# perspection-rf-v1.net
KiCad netlist of a schematic drawn in EAGLE
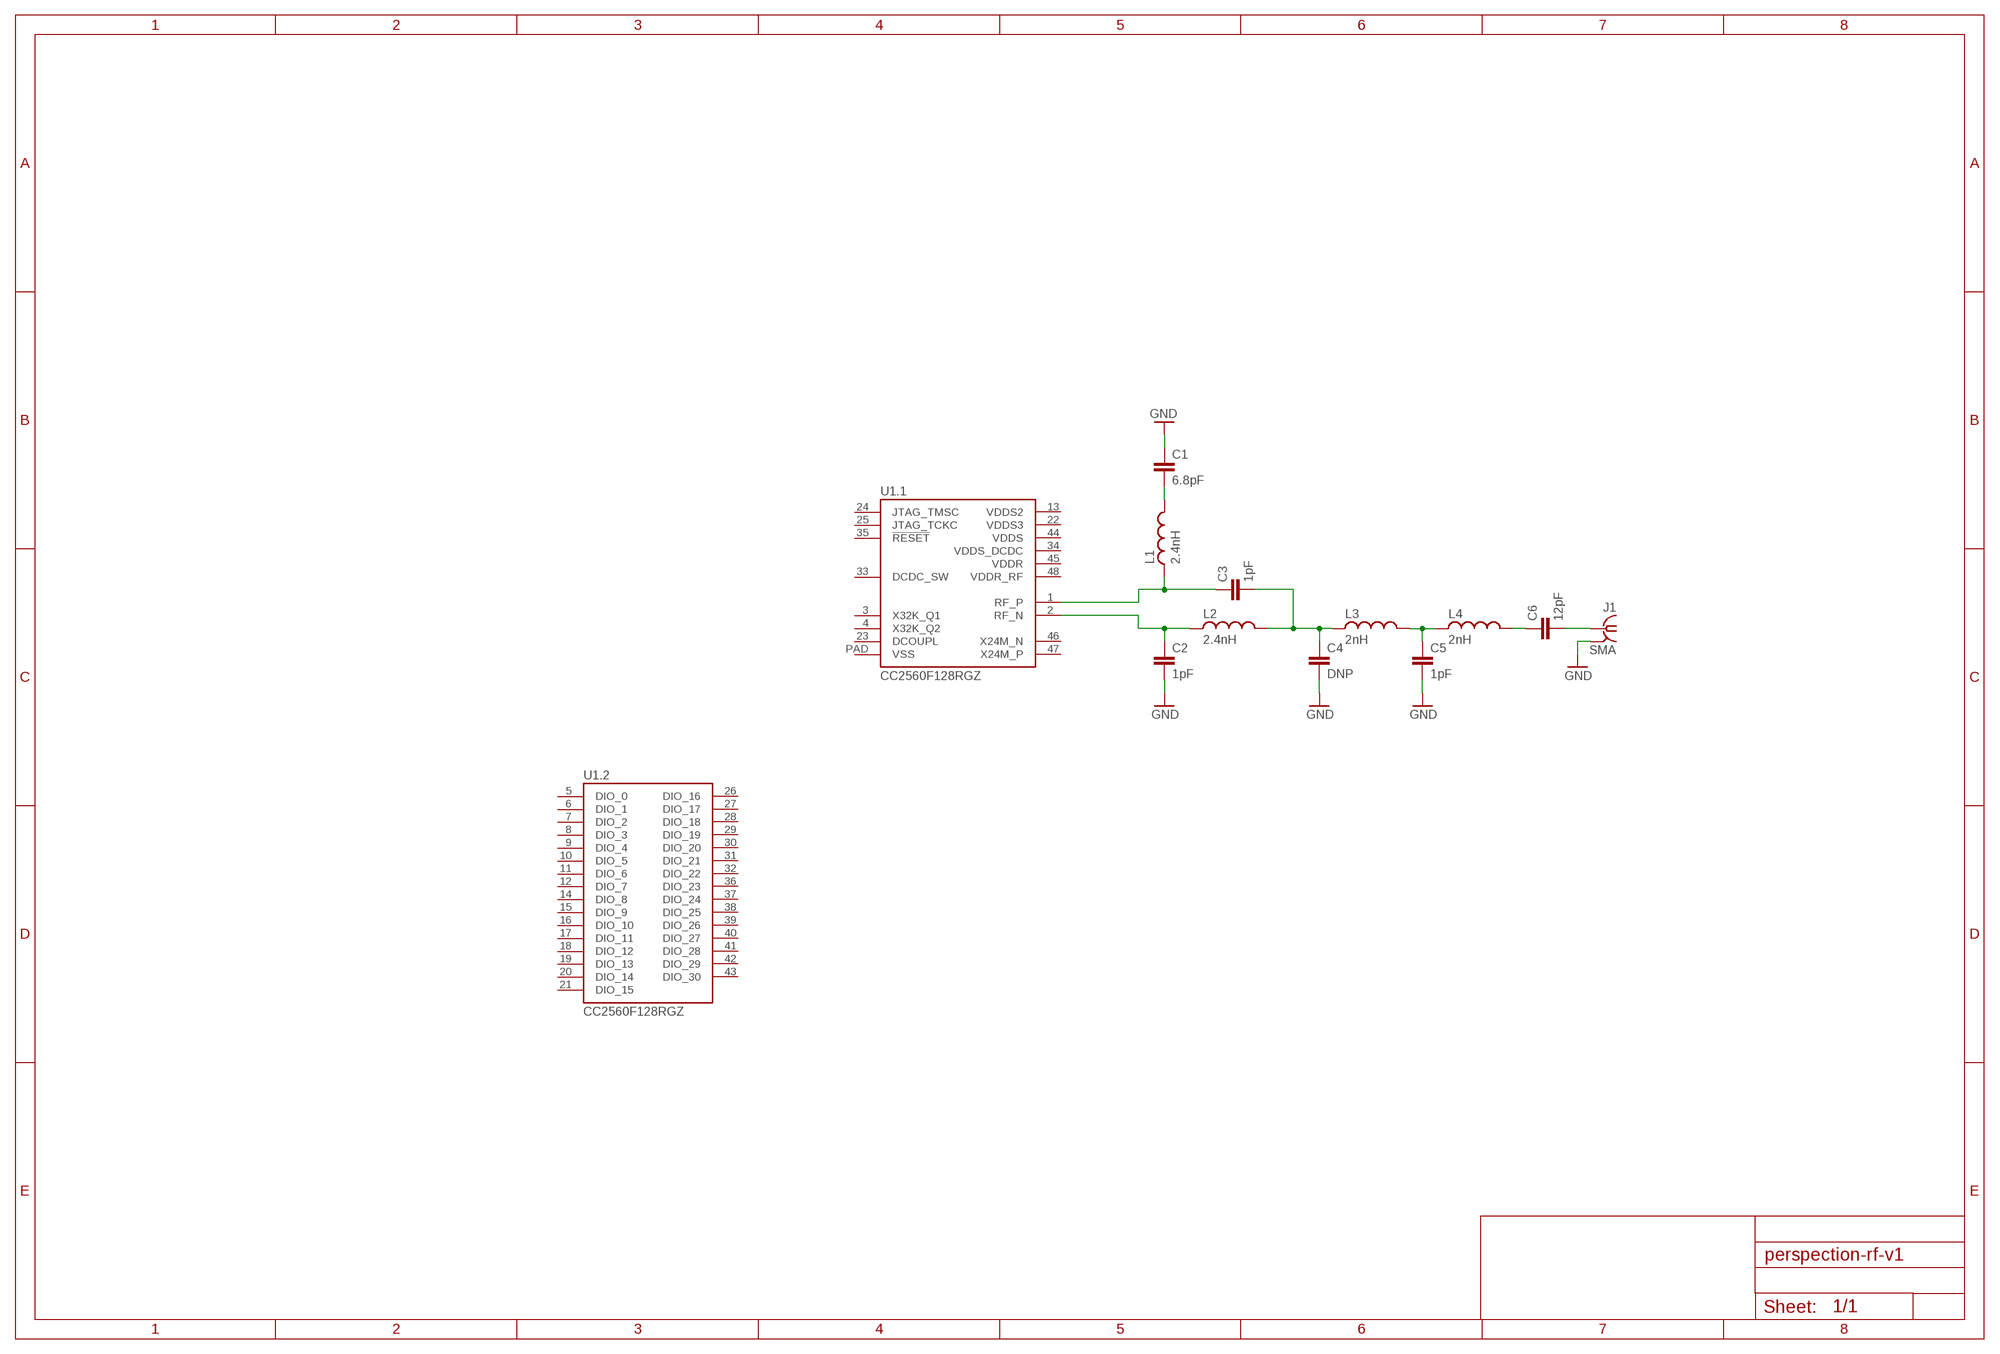
[diagram p0: schematic, sheet 1]

(export (version "E")
  (design (tool "Eeschema 10.0.6"))
  (components
    (comp (ref "C1")
      (value "6.8pF")
      (footprint "eagle-import:C0402")
      (libsource (lib "eagle-import") (part "C0402"))
    )
    (comp (ref "C2")
      (value "1pF")
      (footprint "eagle-import:C0402")
      (libsource (lib "eagle-import") (part "C0402"))
    )
    (comp (ref "C3")
      (value "1pF")
      (footprint "eagle-import:C0402")
      (libsource (lib "eagle-import") (part "C0402"))
    )
    (comp (ref "C4")
      (value "DNP")
      (footprint "eagle-import:C0402")
      (libsource (lib "eagle-import") (part "C0402"))
    )
    (comp (ref "C5")
      (value "1pF")
      (footprint "eagle-import:C0402")
      (libsource (lib "eagle-import") (part "C0402"))
    )
    (comp (ref "C6")
      (value "12pF")
      (footprint "eagle-import:C0402")
      (libsource (lib "eagle-import") (part "C0402"))
    )
    (comp (ref "J1")
      (value "SMA")
      (footprint "eagle-import:SMA-VERT")
      (libsource (lib "eagle-import") (part "SMA"))
    )
    (comp (ref "L1")
      (value "2.4nH")
      (footprint "eagle-import:L0402")
      (libsource (lib "eagle-import") (part "L0402"))
    )
    (comp (ref "L2")
      (value "2.4nH")
      (footprint "eagle-import:L0402")
      (libsource (lib "eagle-import") (part "L0402"))
    )
    (comp (ref "L3")
      (value "2nH")
      (footprint "eagle-import:L0402")
      (libsource (lib "eagle-import") (part "L0402"))
    )
    (comp (ref "L4")
      (value "2nH")
      (footprint "eagle-import:L0402")
      (libsource (lib "eagle-import") (part "L0402"))
    )
    (comp (ref "U1")
      (value "CC2560F128RGZ")
      (footprint "eagle-import:TI-VQFN-48")
      (libsource (lib "eagle-import") (part "CC2560F128RGZ"))
    )
  )
  (nets
    (net (code "1") (name "GND") (class "Default")
      (node (ref "C1") (pin "1") (pinfunction "1_1") (pintype "passive"))
      (node (ref "C2") (pin "2") (pinfunction "2_2") (pintype "passive"))
      (node (ref "C4") (pin "2") (pinfunction "2_2") (pintype "passive"))
      (node (ref "C5") (pin "2") (pinfunction "2_2") (pintype "passive"))
      (node (ref "J1") (pin "NEG1") (pinfunction "NEG_NEG1") (pintype "passive"))
      (node (ref "J1") (pin "NEG2") (pinfunction "NEG_NEG2") (pintype "passive"))
      (node (ref "J1") (pin "NEG3") (pinfunction "NEG_NEG3") (pintype "passive"))
      (node (ref "J1") (pin "NEG4") (pinfunction "NEG_NEG4") (pintype "passive"))
    )
    (net (code "2") (name "Net-(C1-Pad2)") (class "Default")
      (node (ref "C1") (pin "2") (pinfunction "2_2") (pintype "passive"))
      (node (ref "L1") (pin "2") (pinfunction "2_2") (pintype "passive"))
    )
    (net (code "3") (name "Net-(C3-Pad2)") (class "Default")
      (node (ref "C3") (pin "2") (pinfunction "2_2") (pintype "passive"))
      (node (ref "C4") (pin "1") (pinfunction "1_1") (pintype "passive"))
      (node (ref "L2") (pin "2") (pinfunction "2_2") (pintype "passive"))
      (node (ref "L3") (pin "1") (pinfunction "1_1") (pintype "passive"))
    )
    (net (code "4") (name "Net-(C5-Pad1)") (class "Default")
      (node (ref "C5") (pin "1") (pinfunction "1_1") (pintype "passive"))
      (node (ref "L3") (pin "2") (pinfunction "2_2") (pintype "passive"))
      (node (ref "L4") (pin "1") (pinfunction "1_1") (pintype "passive"))
    )
    (net (code "5") (name "Net-(C6-Pad1)") (class "Default")
      (node (ref "C6") (pin "1") (pinfunction "1_1") (pintype "passive"))
      (node (ref "L4") (pin "2") (pinfunction "2_2") (pintype "passive"))
    )
    (net (code "6") (name "Net-(C6-Pad2)") (class "Default")
      (node (ref "C6") (pin "2") (pinfunction "2_2") (pintype "passive"))
      (node (ref "J1") (pin "POS") (pinfunction "POS_POS") (pintype "passive"))
    )
    (net (code "7") (name "Net-(U1A-RF_N)") (class "Default")
      (node (ref "C2") (pin "1") (pinfunction "1_1") (pintype "passive"))
      (node (ref "L2") (pin "1") (pinfunction "1_1") (pintype "passive"))
      (node (ref "U1") (pin "2") (pinfunction "RF_N_2") (pintype "bidirectional"))
    )
    (net (code "8") (name "Net-(U1A-RF_P)") (class "Default")
      (node (ref "C3") (pin "1") (pinfunction "1_1") (pintype "passive"))
      (node (ref "L1") (pin "1") (pinfunction "1_1") (pintype "passive"))
      (node (ref "U1") (pin "1") (pinfunction "RF_P_1") (pintype "bidirectional"))
    )
    (net (code "9") (name "unconnected-(U1A-DCDC_SW-Pad33)") (class "Default")
      (node (ref "U1") (pin "33") (pinfunction "DCDC_SW_33") (pintype "bidirectional"))
    )
    (net (code "10") (name "unconnected-(U1A-DCOUPL-Pad23)") (class "Default")
      (node (ref "U1") (pin "23") (pinfunction "DCOUPL_23") (pintype "bidirectional"))
    )
    (net (code "11") (name "unconnected-(U1A-JTAG_TCKC-Pad25)") (class "Default")
      (node (ref "U1") (pin "25") (pinfunction "JTAG_TCKC_25") (pintype "bidirectional"))
    )
    (net (code "12") (name "unconnected-(U1A-JTAG_TMSC-Pad24)") (class "Default")
      (node (ref "U1") (pin "24") (pinfunction "JTAG_TMSC_24") (pintype "bidirectional"))
    )
    (net (code "13") (name "unconnected-(U1A-VDDR-Pad45)") (class "Default")
      (node (ref "U1") (pin "45") (pinfunction "VDDR_45") (pintype "bidirectional"))
    )
    (net (code "14") (name "unconnected-(U1A-VDDR_RF-Pad48)") (class "Default")
      (node (ref "U1") (pin "48") (pinfunction "VDDR_RF_48") (pintype "bidirectional"))
    )
    (net (code "15") (name "unconnected-(U1A-VDDS-Pad44)") (class "Default")
      (node (ref "U1") (pin "44") (pinfunction "VDDS_44") (pintype "bidirectional"))
    )
    (net (code "16") (name "unconnected-(U1A-VDDS2-Pad13)") (class "Default")
      (node (ref "U1") (pin "13") (pinfunction "VDDS2_13") (pintype "bidirectional"))
    )
    (net (code "17") (name "unconnected-(U1A-VDDS3-Pad22)") (class "Default")
      (node (ref "U1") (pin "22") (pinfunction "VDDS3_22") (pintype "bidirectional"))
    )
    (net (code "18") (name "unconnected-(U1A-VDDS_DCDC-Pad34)") (class "Default")
      (node (ref "U1") (pin "34") (pinfunction "VDDS_DCDC_34") (pintype "bidirectional"))
    )
    (net (code "19") (name "unconnected-(U1A-VSS-PadPAD)") (class "Default")
      (node (ref "U1") (pin "PAD") (pinfunction "VSS_PAD") (pintype "bidirectional"))
    )
    (net (code "20") (name "unconnected-(U1A-X24M_N-Pad46)") (class "Default")
      (node (ref "U1") (pin "46") (pinfunction "X24M_N_46") (pintype "bidirectional"))
    )
    (net (code "21") (name "unconnected-(U1A-X24M_P-Pad47)") (class "Default")
      (node (ref "U1") (pin "47") (pinfunction "X24M_P_47") (pintype "bidirectional"))
    )
    (net (code "22") (name "unconnected-(U1A-X32K_Q1-Pad3)") (class "Default")
      (node (ref "U1") (pin "3") (pinfunction "X32K_Q1_3") (pintype "bidirectional"))
    )
    (net (code "23") (name "unconnected-(U1A-X32K_Q2-Pad4)") (class "Default")
      (node (ref "U1") (pin "4") (pinfunction "X32K_Q2_4") (pintype "bidirectional"))
    )
    (net (code "24") (name "unconnected-(U1A-~{RESET}-Pad35)") (class "Default")
      (node (ref "U1") (pin "35") (pinfunction "~{RESET}_35") (pintype "bidirectional"))
    )
    (net (code "25") (name "unconnected-(U1B-DIO_0-Pad5)") (class "Default")
      (node (ref "U1") (pin "5") (pinfunction "DIO_0_5") (pintype "bidirectional"))
    )
    (net (code "26") (name "unconnected-(U1B-DIO_1-Pad6)") (class "Default")
      (node (ref "U1") (pin "6") (pinfunction "DIO_1_6") (pintype "bidirectional"))
    )
    (net (code "27") (name "unconnected-(U1B-DIO_2-Pad7)") (class "Default")
      (node (ref "U1") (pin "7") (pinfunction "DIO_2_7") (pintype "bidirectional"))
    )
    (net (code "28") (name "unconnected-(U1B-DIO_3-Pad8)") (class "Default")
      (node (ref "U1") (pin "8") (pinfunction "DIO_3_8") (pintype "bidirectional"))
    )
    (net (code "29") (name "unconnected-(U1B-DIO_4-Pad9)") (class "Default")
      (node (ref "U1") (pin "9") (pinfunction "DIO_4_9") (pintype "bidirectional"))
    )
    (net (code "30") (name "unconnected-(U1B-DIO_5-Pad10)") (class "Default")
      (node (ref "U1") (pin "10") (pinfunction "DIO_5_10") (pintype "bidirectional"))
    )
    (net (code "31") (name "unconnected-(U1B-DIO_6-Pad11)") (class "Default")
      (node (ref "U1") (pin "11") (pinfunction "DIO_6_11") (pintype "bidirectional"))
    )
    (net (code "32") (name "unconnected-(U1B-DIO_7-Pad12)") (class "Default")
      (node (ref "U1") (pin "12") (pinfunction "DIO_7_12") (pintype "bidirectional"))
    )
    (net (code "33") (name "unconnected-(U1B-DIO_8-Pad14)") (class "Default")
      (node (ref "U1") (pin "14") (pinfunction "DIO_8_14") (pintype "bidirectional"))
    )
    (net (code "34") (name "unconnected-(U1B-DIO_9-Pad15)") (class "Default")
      (node (ref "U1") (pin "15") (pinfunction "DIO_9_15") (pintype "bidirectional"))
    )
    (net (code "35") (name "unconnected-(U1B-DIO_10-Pad16)") (class "Default")
      (node (ref "U1") (pin "16") (pinfunction "DIO_10_16") (pintype "bidirectional"))
    )
    (net (code "36") (name "unconnected-(U1B-DIO_11-Pad17)") (class "Default")
      (node (ref "U1") (pin "17") (pinfunction "DIO_11_17") (pintype "bidirectional"))
    )
    (net (code "37") (name "unconnected-(U1B-DIO_12-Pad18)") (class "Default")
      (node (ref "U1") (pin "18") (pinfunction "DIO_12_18") (pintype "bidirectional"))
    )
    (net (code "38") (name "unconnected-(U1B-DIO_13-Pad19)") (class "Default")
      (node (ref "U1") (pin "19") (pinfunction "DIO_13_19") (pintype "bidirectional"))
    )
    (net (code "39") (name "unconnected-(U1B-DIO_14-Pad20)") (class "Default")
      (node (ref "U1") (pin "20") (pinfunction "DIO_14_20") (pintype "bidirectional"))
    )
    (net (code "40") (name "unconnected-(U1B-DIO_15-Pad21)") (class "Default")
      (node (ref "U1") (pin "21") (pinfunction "DIO_15_21") (pintype "bidirectional"))
    )
    (net (code "41") (name "unconnected-(U1B-DIO_16-Pad26)") (class "Default")
      (node (ref "U1") (pin "26") (pinfunction "DIO_16_26") (pintype "bidirectional"))
    )
    (net (code "42") (name "unconnected-(U1B-DIO_17-Pad27)") (class "Default")
      (node (ref "U1") (pin "27") (pinfunction "DIO_17_27") (pintype "bidirectional"))
    )
    (net (code "43") (name "unconnected-(U1B-DIO_18-Pad28)") (class "Default")
      (node (ref "U1") (pin "28") (pinfunction "DIO_18_28") (pintype "bidirectional"))
    )
    (net (code "44") (name "unconnected-(U1B-DIO_19-Pad29)") (class "Default")
      (node (ref "U1") (pin "29") (pinfunction "DIO_19_29") (pintype "bidirectional"))
    )
    (net (code "45") (name "unconnected-(U1B-DIO_20-Pad30)") (class "Default")
      (node (ref "U1") (pin "30") (pinfunction "DIO_20_30") (pintype "bidirectional"))
    )
    (net (code "46") (name "unconnected-(U1B-DIO_21-Pad31)") (class "Default")
      (node (ref "U1") (pin "31") (pinfunction "DIO_21_31") (pintype "bidirectional"))
    )
    (net (code "47") (name "unconnected-(U1B-DIO_22-Pad32)") (class "Default")
      (node (ref "U1") (pin "32") (pinfunction "DIO_22_32") (pintype "bidirectional"))
    )
    (net (code "48") (name "unconnected-(U1B-DIO_23-Pad36)") (class "Default")
      (node (ref "U1") (pin "36") (pinfunction "DIO_23_36") (pintype "bidirectional"))
    )
    (net (code "49") (name "unconnected-(U1B-DIO_24-Pad37)") (class "Default")
      (node (ref "U1") (pin "37") (pinfunction "DIO_24_37") (pintype "bidirectional"))
    )
    (net (code "50") (name "unconnected-(U1B-DIO_25-Pad38)") (class "Default")
      (node (ref "U1") (pin "38") (pinfunction "DIO_25_38") (pintype "bidirectional"))
    )
    (net (code "51") (name "unconnected-(U1B-DIO_26-Pad39)") (class "Default")
      (node (ref "U1") (pin "39") (pinfunction "DIO_26_39") (pintype "bidirectional"))
    )
    (net (code "52") (name "unconnected-(U1B-DIO_27-Pad40)") (class "Default")
      (node (ref "U1") (pin "40") (pinfunction "DIO_27_40") (pintype "bidirectional"))
    )
    (net (code "53") (name "unconnected-(U1B-DIO_28-Pad41)") (class "Default")
      (node (ref "U1") (pin "41") (pinfunction "DIO_28_41") (pintype "bidirectional"))
    )
    (net (code "54") (name "unconnected-(U1B-DIO_29-Pad42)") (class "Default")
      (node (ref "U1") (pin "42") (pinfunction "DIO_29_42") (pintype "bidirectional"))
    )
    (net (code "55") (name "unconnected-(U1B-DIO_30-Pad43)") (class "Default")
      (node (ref "U1") (pin "43") (pinfunction "DIO_30_43") (pintype "bidirectional"))
    )
  )
)
